# 14_Clocks.net
KiCad netlist of a schematic drawn in Altium Designer
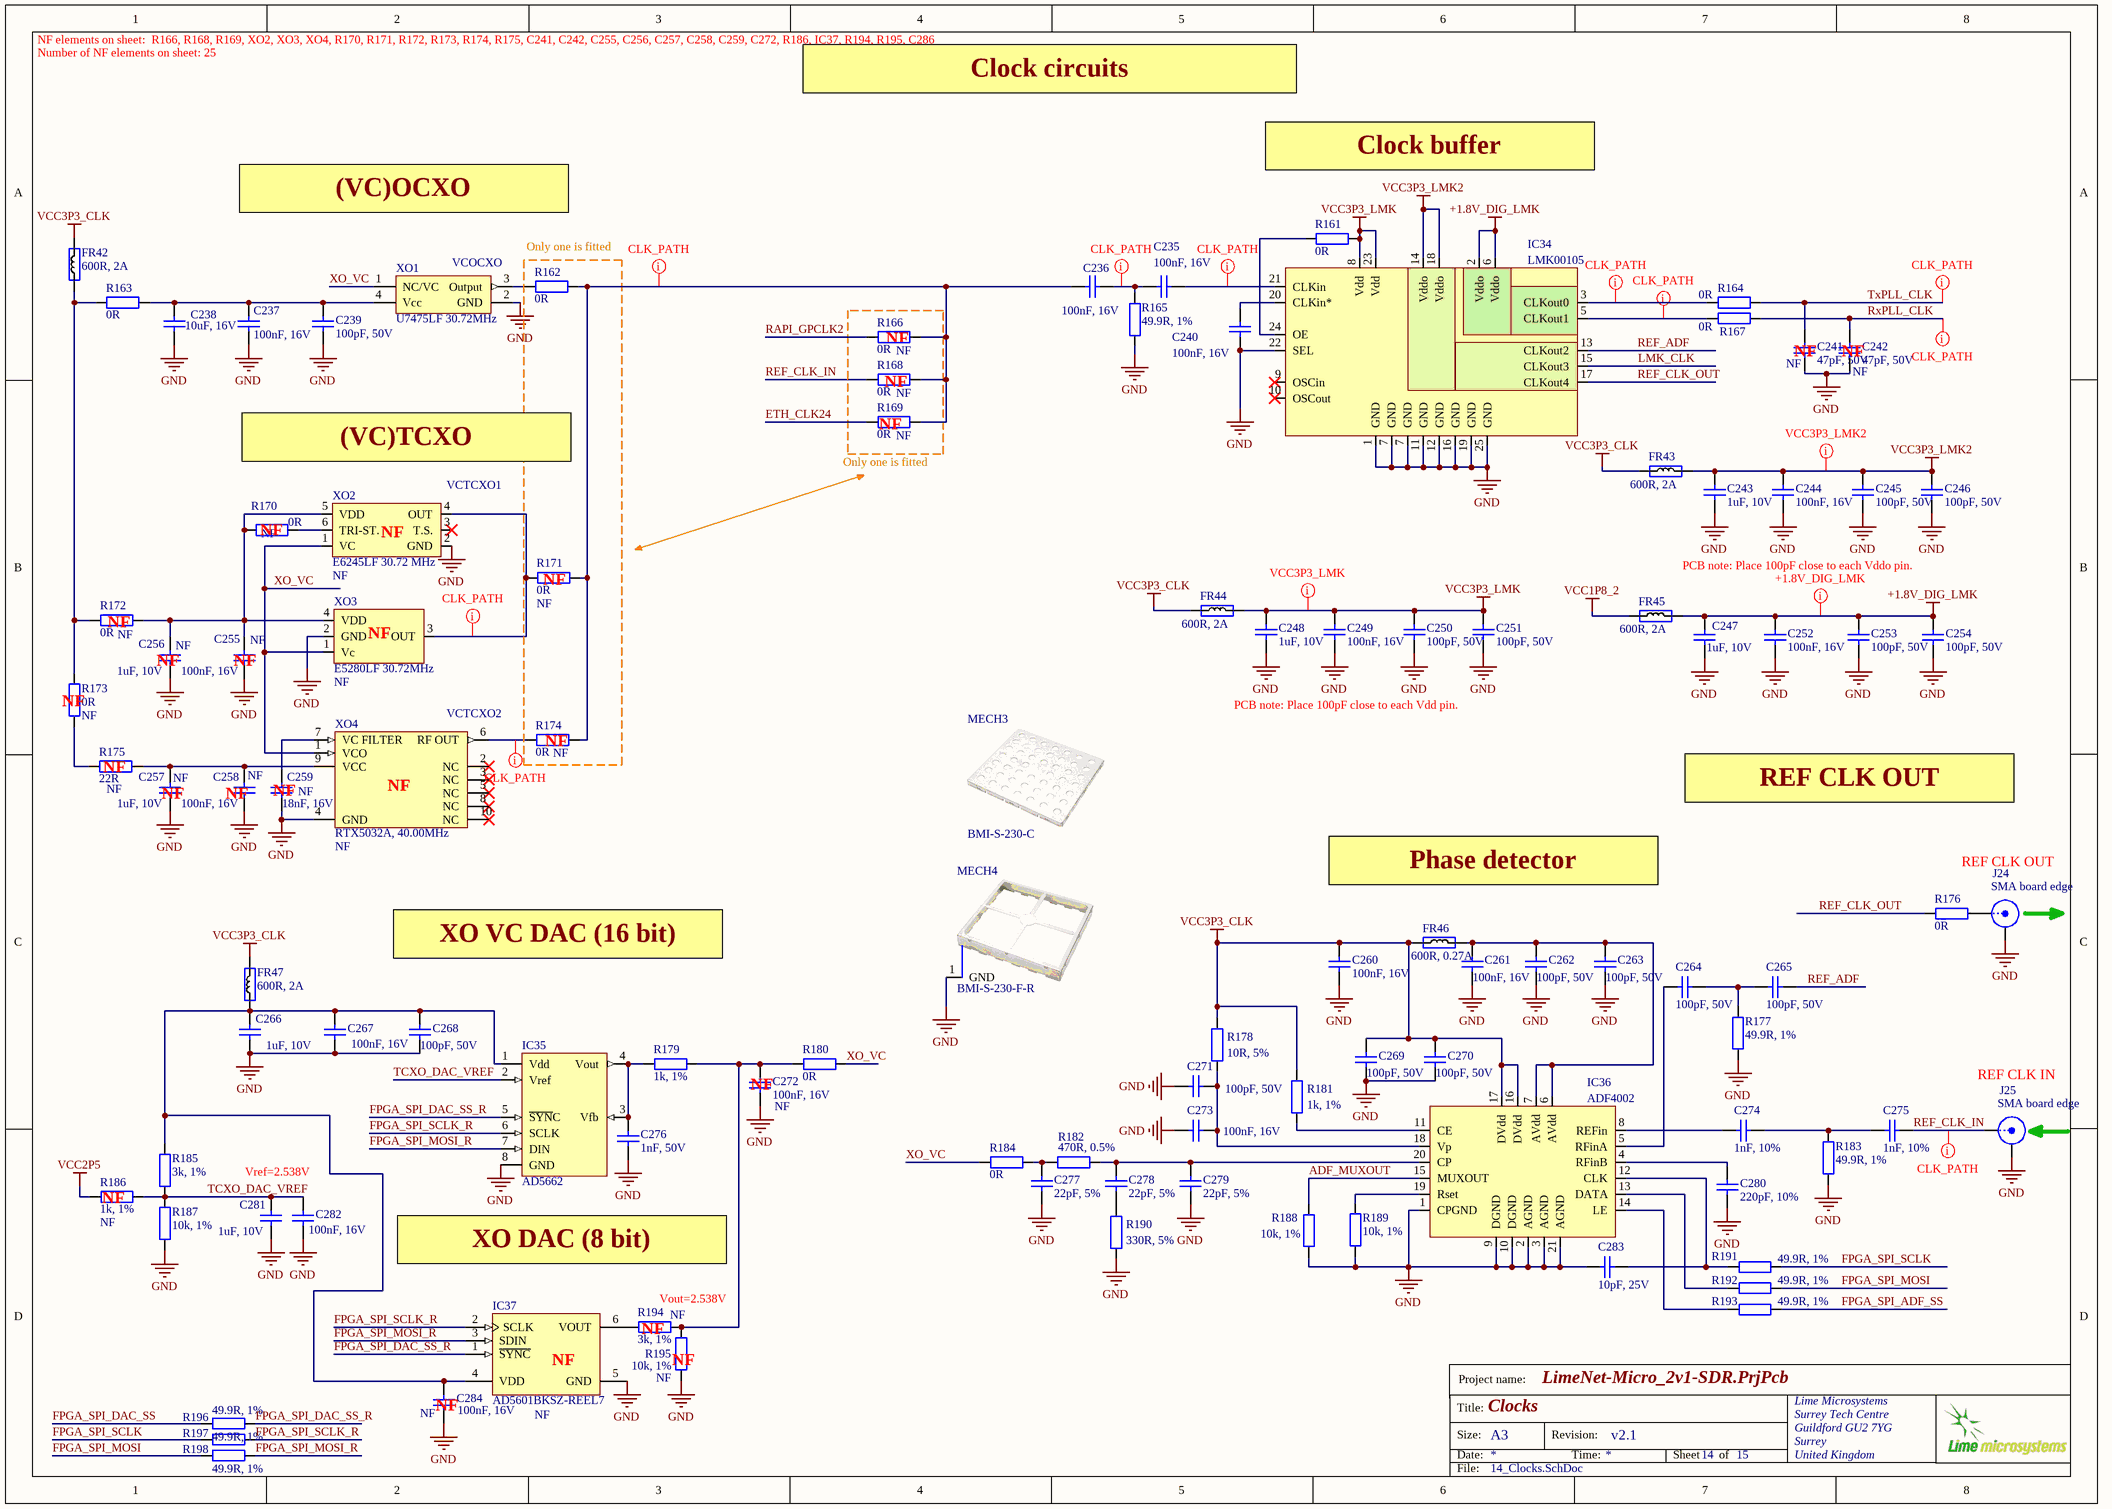
[diagram p0: 14_Clocks.SchDoc]

(export (version "E")
  (design (tool "Eeschema 10.0.6"))
  (components
    (comp (ref "C235")
      (value "100nF, 16V")
      (footprint "CAP0402")
      (fields
        (field (name "MANUFACTURER") "Murata Electronics")
        (field (name "TOLERANCE") "10 %")
        (field (name "MANUFACTURER PART NUMBER") "GRM155R71C104KA88D")
      )
      (libsource (lib "LimeMicroAltiumLib_schLib") (part "Cap_0402"))
    )
    (comp (ref "C236")
      (value "100nF, 16V")
      (footprint "CAP0402")
      (fields
        (field (name "MANUFACTURER") "Murata Electronics")
        (field (name "TOLERANCE") "10 %")
        (field (name "MANUFACTURER PART NUMBER") "GRM155R71C104KA88D")
      )
      (libsource (lib "LimeMicroAltiumLib_schLib") (part "Cap_0402"))
    )
    (comp (ref "C237")
      (value "100nF, 16V")
      (footprint "CAP0402")
      (fields
        (field (name "MANUFACTURER") "Murata Electronics")
        (field (name "TOLERANCE") "10 %")
        (field (name "MANUFACTURER PART NUMBER") "GRM155R71C104KA88D")
      )
      (libsource (lib "LimeMicroAltiumLib_schLib") (part "Cap_0402"))
    )
    (comp (ref "C238")
      (value "10uF, 16V")
      (footprint "CAP0603")
      (fields (field (name "MANUFACTURER") "Yageo") (field (name "TOLERANCE") "±20%"))
      (libsource (lib "LimeMicroAltiumLib_schLib") (part "Cap_0603"))
    )
    (comp (ref "C239")
      (value "100pF, 50V")
      (footprint "CAP0402")
      (fields (field (name "TOLERANCE") "±5%") (field (name "MANUFACTURER") "Yageo"))
      (libsource (lib "LimeMicroAltiumLib_schLib") (part "Cap_0402"))
    )
    (comp (ref "C240")
      (value "100nF, 16V")
      (footprint "CAP0402")
      (fields
        (field (name "MANUFACTURER") "Murata Electronics")
        (field (name "TOLERANCE") "10 %")
        (field (name "MANUFACTURER PART NUMBER") "GRM155R71C104KA88D")
      )
      (libsource (lib "LimeMicroAltiumLib_schLib") (part "Cap_0402"))
    )
    (comp (ref "C241")
      (value "47pF, 50V")
      (footprint "CAP0402")
      (fields
        (field (name "TOLERANCE") "±1%")
        (field (name "MANUFACTURER") "TDK Corporation")
        (field (name "ASSEMBLY INFO") "NF")
      )
      (libsource (lib "LimeMicroAltiumLib_schLib") (part "Cap_0402"))
    )
    (comp (ref "C242")
      (value "47pF, 50V")
      (footprint "CAP0402")
      (fields
        (field (name "TOLERANCE") "±1%")
        (field (name "MANUFACTURER") "TDK Corporation")
        (field (name "ASSEMBLY INFO") "NF")
      )
      (libsource (lib "LimeMicroAltiumLib_schLib") (part "Cap_0402"))
    )
    (comp (ref "C243")
      (value "1uF, 10V")
      (footprint "CAP0402")
      (description "CAP CER 1UF 10V X5R 0402")
      (fields (field (name "MANUFACTURER") "Yageo") (field (name "TOLERANCE") "±20%"))
      (libsource (lib "LimeMicroAltiumLib_schLib") (part "Cap_0402"))
    )
    (comp (ref "C244")
      (value "100nF, 16V")
      (footprint "CAP0402")
      (fields
        (field (name "MANUFACTURER") "Murata Electronics")
        (field (name "TOLERANCE") "10 %")
        (field (name "MANUFACTURER PART NUMBER") "GRM155R71C104KA88D")
      )
      (libsource (lib "LimeMicroAltiumLib_schLib") (part "Cap_0402"))
    )
    (comp (ref "C245")
      (value "100pF, 50V")
      (footprint "CAP0402")
      (fields (field (name "MANUFACTURER") "Yageo") (field (name "TOLERANCE") "±5%"))
      (libsource (lib "LimeMicroAltiumLib_schLib") (part "Cap_0402"))
    )
    (comp (ref "C246")
      (value "100pF, 50V")
      (footprint "CAP0402")
      (fields (field (name "MANUFACTURER") "Yageo") (field (name "TOLERANCE") "±5%"))
      (libsource (lib "LimeMicroAltiumLib_schLib") (part "Cap_0402"))
    )
    (comp (ref "C247")
      (value "1uF, 10V")
      (footprint "CAP0402")
      (description "CAP CER 1UF 10V X5R 0402")
      (fields (field (name "MANUFACTURER") "Yageo") (field (name "TOLERANCE") "±20%"))
      (libsource (lib "LimeMicroAltiumLib_schLib") (part "Cap_0402"))
    )
    (comp (ref "C248")
      (value "1uF, 10V")
      (footprint "CAP0402")
      (description "CAP CER 1UF 10V X5R 0402")
      (fields (field (name "MANUFACTURER") "Yageo") (field (name "TOLERANCE") "±20%"))
      (libsource (lib "LimeMicroAltiumLib_schLib") (part "Cap_0402"))
    )
    (comp (ref "C249")
      (value "100nF, 16V")
      (footprint "CAP0402")
      (fields
        (field (name "MANUFACTURER") "Murata Electronics")
        (field (name "TOLERANCE") "10 %")
        (field (name "MANUFACTURER PART NUMBER") "GRM155R71C104KA88D")
      )
      (libsource (lib "LimeMicroAltiumLib_schLib") (part "Cap_0402"))
    )
    (comp (ref "C250")
      (value "100pF, 50V")
      (footprint "CAP0402")
      (fields (field (name "MANUFACTURER") "Yageo") (field (name "TOLERANCE") "±5%"))
      (libsource (lib "LimeMicroAltiumLib_schLib") (part "Cap_0402"))
    )
    (comp (ref "C251")
      (value "100pF, 50V")
      (footprint "CAP0402")
      (fields (field (name "MANUFACTURER") "Yageo") (field (name "TOLERANCE") "±5%"))
      (libsource (lib "LimeMicroAltiumLib_schLib") (part "Cap_0402"))
    )
    (comp (ref "C252")
      (value "100nF, 16V")
      (footprint "CAP0402")
      (fields
        (field (name "MANUFACTURER") "Murata Electronics")
        (field (name "TOLERANCE") "10 %")
        (field (name "MANUFACTURER PART NUMBER") "GRM155R71C104KA88D")
      )
      (libsource (lib "LimeMicroAltiumLib_schLib") (part "Cap_0402"))
    )
    (comp (ref "C253")
      (value "100pF, 50V")
      (footprint "CAP0402")
      (fields (field (name "MANUFACTURER") "Yageo") (field (name "TOLERANCE") "±5%"))
      (libsource (lib "LimeMicroAltiumLib_schLib") (part "Cap_0402"))
    )
    (comp (ref "C254")
      (value "100pF, 50V")
      (footprint "CAP0402")
      (fields (field (name "MANUFACTURER") "Yageo") (field (name "TOLERANCE") "±5%"))
      (libsource (lib "LimeMicroAltiumLib_schLib") (part "Cap_0402"))
    )
    (comp (ref "C255")
      (value "100nF, 16V")
      (footprint "CAP0402")
      (fields
        (field (name "ASSEMBLY INFO") "NF")
        (field (name "MANUFACTURER") "Murata Electronics")
        (field (name "TOLERANCE") "10 %")
        (field (name "MANUFACTURER PART NUMBER") "GRM155R71C104KA88D")
      )
      (libsource (lib "LimeMicroAltiumLib_schLib") (part "Cap_0402"))
    )
    (comp (ref "C256")
      (value "1uF, 10V")
      (footprint "CAP0402")
      (description "CAP CER 1UF 10V X5R 0402")
      (fields
        (field (name "ASSEMBLY INFO") "NF")
        (field (name "MANUFACTURER") "Yageo")
        (field (name "TOLERANCE") "±20%")
      )
      (libsource (lib "LimeMicroAltiumLib_schLib") (part "Cap_0402"))
    )
    (comp (ref "C257")
      (value "1uF, 10V")
      (footprint "CAP0402")
      (description "CAP CER 1UF 10V X5R 0402")
      (fields
        (field (name "ASSEMBLY INFO") "NF")
        (field (name "MANUFACTURER") "Yageo")
        (field (name "TOLERANCE") "±20%")
      )
      (libsource (lib "LimeMicroAltiumLib_schLib") (part "Cap_0402"))
    )
    (comp (ref "C258")
      (value "100nF, 16V")
      (footprint "CAP0402")
      (fields
        (field (name "ASSEMBLY INFO") "NF")
        (field (name "MANUFACTURER") "Murata Electronics")
        (field (name "TOLERANCE") "10 %")
        (field (name "MANUFACTURER PART NUMBER") "GRM155R71C104KA88D")
      )
      (libsource (lib "LimeMicroAltiumLib_schLib") (part "Cap_0402"))
    )
    (comp (ref "C259")
      (value "18nF, 16V")
      (footprint "CAP0402")
      (fields
        (field (name "ASSEMBLY INFO") "NF")
        (field (name "MANUFACTURER") "Yageo")
        (field (name "TOLERANCE") "±10%")
      )
      (libsource (lib "LimeMicroAltiumLib_schLib") (part "Cap_0402"))
    )
    (comp (ref "C260")
      (value "100nF, 16V")
      (footprint "CAP0402")
      (fields
        (field (name "MANUFACTURER") "Murata Electronics")
        (field (name "TOLERANCE") "10 %")
        (field (name "MANUFACTURER PART NUMBER") "GRM155R71C104KA88D")
      )
      (libsource (lib "LimeMicroAltiumLib_schLib") (part "Cap_0402"))
    )
    (comp (ref "C261")
      (value "100nF, 16V")
      (footprint "CAP0402")
      (fields
        (field (name "MANUFACTURER") "Murata Electronics")
        (field (name "TOLERANCE") "10 %")
        (field (name "MANUFACTURER PART NUMBER") "GRM155R71C104KA88D")
      )
      (libsource (lib "LimeMicroAltiumLib_schLib") (part "Cap_0402"))
    )
    (comp (ref "C262")
      (value "100pF, 50V")
      (footprint "CAP0402")
      (fields (field (name "MANUFACTURER") "Yageo") (field (name "TOLERANCE") "±5%"))
      (libsource (lib "LimeMicroAltiumLib_schLib") (part "Cap_0402"))
    )
    (comp (ref "C263")
      (value "100pF, 50V")
      (footprint "CAP0402")
      (fields (field (name "MANUFACTURER") "Yageo") (field (name "TOLERANCE") "±5%"))
      (libsource (lib "LimeMicroAltiumLib_schLib") (part "Cap_0402"))
    )
    (comp (ref "C264")
      (value "100pF, 50V")
      (footprint "CAP0402")
      (fields (field (name "MANUFACTURER") "Yageo") (field (name "TOLERANCE") "±5%"))
      (libsource (lib "LimeMicroAltiumLib_schLib") (part "Cap_0402"))
    )
    (comp (ref "C265")
      (value "100pF, 50V")
      (footprint "CAP0402")
      (fields (field (name "MANUFACTURER") "Yageo") (field (name "TOLERANCE") "±5%"))
      (libsource (lib "LimeMicroAltiumLib_schLib") (part "Cap_0402"))
    )
    (comp (ref "C266")
      (value "1uF, 10V")
      (footprint "CAP0402")
      (description "CAP CER 1UF 10V X5R 0402")
      (fields (field (name "MANUFACTURER") "Yageo") (field (name "TOLERANCE") "±20%"))
      (libsource (lib "LimeMicroAltiumLib_schLib") (part "Cap_0402"))
    )
    (comp (ref "C267")
      (value "100nF, 16V")
      (footprint "CAP0402")
      (fields
        (field (name "TOLERANCE") "10 %")
        (field (name "MANUFACTURER") "Murata Electronics")
        (field (name "MANUFACTURER PART NUMBER") "GRM155R71C104KA88D")
      )
      (libsource (lib "LimeFPGAboard_schLib") (part "Cap_0603"))
    )
    (comp (ref "C268")
      (value "100pF, 50V")
      (footprint "CAP0402")
      (fields (field (name "MANUFACTURER") "Yageo") (field (name "TOLERANCE") "±5%"))
      (libsource (lib "LimeMicroAltiumLib_schLib") (part "Cap_0402"))
    )
    (comp (ref "C269")
      (value "100pF, 50V")
      (footprint "CAP0402")
      (fields (field (name "MANUFACTURER") "Yageo") (field (name "TOLERANCE") "±5%"))
      (libsource (lib "LimeMicroAltiumLib_schLib") (part "Cap_0402"))
    )
    (comp (ref "C270")
      (value "100pF, 50V")
      (footprint "CAP0402")
      (fields (field (name "MANUFACTURER") "Yageo") (field (name "TOLERANCE") "±5%"))
      (libsource (lib "LimeMicroAltiumLib_schLib") (part "Cap_0402"))
    )
    (comp (ref "C271")
      (value "100pF, 50V")
      (footprint "CAP0402")
      (fields (field (name "MANUFACTURER") "Yageo") (field (name "TOLERANCE") "±5%"))
      (libsource (lib "LimeMicroAltiumLib_schLib") (part "Cap_0402"))
    )
    (comp (ref "C272")
      (value "100nF, 16V")
      (footprint "CAP0402")
      (fields
        (field (name "ASSEMBLY INFO") "NF")
        (field (name "MANUFACTURER") "Murata Electronics")
        (field (name "TOLERANCE") "10 %")
        (field (name "MANUFACTURER PART NUMBER") "GRM155R71C104KA88D")
      )
      (libsource (lib "LimeMicroAltiumLib_schLib") (part "Cap_0402"))
    )
    (comp (ref "C273")
      (value "100nF, 16V")
      (footprint "CAP0402")
      (fields
        (field (name "MANUFACTURER") "Murata Electronics")
        (field (name "TOLERANCE") "10 %")
        (field (name "MANUFACTURER PART NUMBER") "GRM155R71C104KA88D")
      )
      (libsource (lib "LimeMicroAltiumLib_schLib") (part "Cap_0402"))
    )
    (comp (ref "C274")
      (value "1nF, 10%")
      (footprint "CAP0402")
      (fields (field (name "TOLERANCE") "10 %") (field (name "MANUFACTURER") "Murata Electronics"))
      (libsource (lib "LimeMicroAltiumLib_schLib") (part "Cap_0402"))
    )
    (comp (ref "C275")
      (value "1nF, 10%")
      (footprint "CAP0402")
      (fields (field (name "TOLERANCE") "10 %") (field (name "MANUFACTURER") "Murata Electronics"))
      (libsource (lib "LimeMicroAltiumLib_schLib") (part "Cap_0402"))
    )
    (comp (ref "C276")
      (value "1nF, 50V")
      (footprint "CAP0402")
      (fields
        (field (name "TOLERANCE") "±10%")
        (field (name "MANUFACTURER") "Murata Electronics North America")
      )
      (libsource (lib "LimeMicroAltiumLib_schLib") (part "Cap_0402"))
    )
    (comp (ref "C277")
      (value "22pF, 5%")
      (footprint "CAP0402")
      (fields (field (name "TOLERANCE") "±5%") (field (name "MANUFACTURER") "Yageo"))
      (libsource (lib "LimeMicroAltiumLib_schLib") (part "Cap_0402"))
    )
    (comp (ref "C278")
      (value "22pF, 5%")
      (footprint "CAP0402")
      (fields (field (name "TOLERANCE") "±5%") (field (name "MANUFACTURER") "Yageo"))
      (libsource (lib "LimeMicroAltiumLib_schLib") (part "Cap_0402"))
    )
    (comp (ref "C279")
      (value "22pF, 5%")
      (footprint "CAP0402")
      (fields (field (name "TOLERANCE") "±5%") (field (name "MANUFACTURER") "Yageo"))
      (libsource (lib "LimeMicroAltiumLib_schLib") (part "Cap_0402"))
    )
    (comp (ref "C280")
      (value "220pF, 10%")
      (footprint "CAP0402")
      (fields (field (name "MANUFACTURER") "Yageo") (field (name "TOLERANCE") "±10%"))
      (libsource (lib "LimeMicroAltiumLib_schLib") (part "Cap_0402"))
    )
    (comp (ref "C281")
      (value "1uF, 10V")
      (footprint "CAP0402")
      (description "CAP CER 1UF 10V X5R 0402")
      (fields (field (name "MANUFACTURER") "Yageo") (field (name "TOLERANCE") "±20%"))
      (libsource (lib "LimeMicroAltiumLib_schLib") (part "Cap_0402"))
    )
    (comp (ref "C282")
      (value "100nF, 16V")
      (footprint "CAP0402")
      (fields
        (field (name "TOLERANCE") "10 %")
        (field (name "MANUFACTURER") "Murata Electronics")
        (field (name "MANUFACTURER PART NUMBER") "GRM155R71C104KA88D")
      )
      (libsource (lib "LimeFPGAboard_schLib") (part "Cap_0603"))
    )
    (comp (ref "C283")
      (value "10pF, 25V")
      (footprint "CAP0402")
      (fields (field (name "MANUFACTURER") "AVX"))
      (libsource (lib "LimeMicroAltiumLib_schLib") (part "Cap_0402"))
    )
    (comp (ref "C284")
      (value "100nF, 16V")
      (footprint "CAP0402")
      (fields
        (field (name "TOLERANCE") "10 %")
        (field (name "MANUFACTURER") "Murata Electronics")
        (field (name "MANUFACTURER PART NUMBER") "GRM155R71C104KA88D")
        (field (name "ASSEMBLY INFO") "NF")
      )
      (libsource (lib "LimeFPGAboard_schLib") (part "Cap_0603"))
    )
    (comp (ref "FR42")
      (value "600R, 2A")
      (footprint "RES0805")
      (fields (field (name "MANUFACTURER") "TDK Corporation"))
      (libsource (lib "LimeFPGAboard_schLib") (part "Ferrite"))
    )
    (comp (ref "FR43")
      (value "600R, 2A")
      (footprint "RES0805")
      (fields (field (name "MANUFACTURER") "TDK Corporation"))
      (libsource (lib "LimeMicroAltiumLib_schLib") (part "Ferrite"))
    )
    (comp (ref "FR44")
      (value "600R, 2A")
      (footprint "RES0805")
      (fields (field (name "MANUFACTURER") "TDK Corporation"))
      (libsource (lib "LimeMicroAltiumLib_schLib") (part "Ferrite"))
    )
    (comp (ref "FR45")
      (value "600R, 2A")
      (footprint "RES0805")
      (fields (field (name "MANUFACTURER") "TDK Corporation"))
      (libsource (lib "LimeMicroAltiumLib_schLib") (part "Ferrite"))
    )
    (comp (ref "FR46")
      (value "600R, 0.27A")
      (footprint "RES0201")
      (fields (field (name "MANUFACTURER") "Taiyo Yuden"))
      (libsource (lib "LimeMicroAltiumLib_schLib") (part "Ferrite"))
    )
    (comp (ref "FR47")
      (value "600R, 2A")
      (footprint "RES0805")
      (fields (field (name "MANUFACTURER") "TDK Corporation"))
      (libsource (lib "LimeMicroAltiumLib_schLib") (part "Ferrite"))
    )
    (comp (ref "IC34")
      (value "LMK00105")
      (footprint "LMK00105SQ")
      (fields (field (name "MANUFACTURER") "Texas Instruments"))
      (libsource (lib "LimeMicroAltiumLib_schLib") (part "LMK00105"))
    )
    (comp (ref "IC35")
      (value "AD5662")
      (footprint "AD5662_SOT23-8")
      (fields (field (name "MANUFACTURER") "Analog Devices Inc."))
      (libsource (lib "LimeMicroAltiumLib_schLib") (part "AD5662"))
    )
    (comp (ref "IC36")
      (value "ADF4002")
      (footprint "ADF4002")
      (fields (field (name "MANUFACTURER") "Analog Devices Inc"))
      (libsource (lib "LimeMicroAltiumLib_schLib") (part "ADF4002"))
    )
    (comp (ref "IC37")
      (value "AD5601BKSZ-REEL7")
      (footprint "AD5601_SOT23-6")
      (fields
        (field (name "GENERIC PART NUMBER") "AD5601")
        (field (name "MANUFACTURER") "Analog Devices")
        (field (name "ASSEMBLY INFO") "NF")
      )
      (libsource (lib "LimeMicroAltiumLib_schLib") (part "AD5601BKSZ-REEL7"))
    )
    (comp (ref "J24")
      (value "SMA board edge")
      (footprint "SMA_connector_board_edge_SM")
      (description "CONN SMA JACK STR 50OHM EDGE MNT")
      (fields (field (name "MANUFACTURER") "RF Solutions"))
      (libsource (lib "LimeMicroAltiumLib_schLib") (part "RF_IF_connector"))
    )
    (comp (ref "J25")
      (value "SMA board edge")
      (footprint "SMA_connector_board_edge_SM")
      (description "CONN SMA JACK STR 50OHM EDGE MNT")
      (fields (field (name "MANUFACTURER") "RF Solutions"))
      (libsource (lib "LimeMicroAltiumLib_schLib") (part "RF_IF_connector"))
    )
    (comp (ref "MECH3")
      (value "BMI-S-230-C")
      (fields (field (name "MANUFACTURER") "Laird Technologies EMI"))
      (libsource (lib "LimeMicroAltiumLib_schLib_r01") (part "RFI_SHIELD_2_cover"))
    )
    (comp (ref "MECH4")
      (value "BMI-S-230-F-R")
      (footprint "RFI_SHIELD_BMI-S-230-F-R")
      (fields (field (name "MANUFACTURER") "Laird Technologies EMI"))
      (libsource (lib "LimeMicroAltiumLib_schLib_r01") (part "RFI_SHIELD_2_frame"))
    )
    (comp (ref "R161")
      (value "0R")
      (footprint "RES0402")
      (fields (field (name "MANUFACTURER") "Yageo") (field (name "TOLERANCE") "Jumper"))
      (libsource (lib "LimeMicroAltiumLib_schLib") (part "Res_0402"))
    )
    (comp (ref "R162")
      (value "0R")
      (footprint "RES0402_v2")
      (fields (field (name "MANUFACTURER") "Yageo") (field (name "TOLERANCE") "Jumper"))
      (libsource (lib "LimeMicroAltiumLib_schLib") (part "Res_0402"))
    )
    (comp (ref "R163")
      (value "0R")
      (footprint "RES0402")
      (fields (field (name "MANUFACTURER") "Yageo") (field (name "TOLERANCE") "Jumper"))
      (libsource (lib "LimeMicroAltiumLib_schLib") (part "Res_0402"))
    )
    (comp (ref "R164")
      (value "0R")
      (footprint "RES0402")
      (fields (field (name "MANUFACTURER") "Yageo") (field (name "TOLERANCE") "Jumper"))
      (libsource (lib "LimeMicroAltiumLib_schLib") (part "Res_0402"))
    )
    (comp (ref "R165")
      (value "49.9R, 1%")
      (footprint "RES0402")
      (fields
        (field (name "TOLERANCE") "±1%")
        (field (name "MANUFACTURER") "Samsung Electro-Mechanics America, Inc.")
      )
      (libsource (lib "LimeMicroAltiumLib_schLib") (part "Res_0402"))
    )
    (comp (ref "R166")
      (value "0R")
      (footprint "RES0402_v2")
      (fields
        (field (name "ASSEMBLY INFO") "NF")
        (field (name "MANUFACTURER") "Yageo")
        (field (name "TOLERANCE") "Jumper")
      )
      (libsource (lib "LimeMicroAltiumLib_schLib") (part "Res_0402"))
    )
    (comp (ref "R167")
      (value "0R")
      (footprint "RES0402")
      (fields (field (name "MANUFACTURER") "Yageo") (field (name "TOLERANCE") "Jumper"))
      (libsource (lib "LimeMicroAltiumLib_schLib") (part "Res_0402"))
    )
    (comp (ref "R168")
      (value "0R")
      (footprint "RES0402_v2")
      (fields
        (field (name "ASSEMBLY INFO") "NF")
        (field (name "MANUFACTURER") "Yageo")
        (field (name "TOLERANCE") "Jumper")
      )
      (libsource (lib "LimeMicroAltiumLib_schLib") (part "Res_0402"))
    )
    (comp (ref "R169")
      (value "0R")
      (footprint "RES0402_v2")
      (fields
        (field (name "ASSEMBLY INFO") "NF")
        (field (name "MANUFACTURER") "Yageo")
        (field (name "TOLERANCE") "Jumper")
      )
      (libsource (lib "LimeMicroAltiumLib_schLib") (part "Res_0402"))
    )
    (comp (ref "R170")
      (value "0R")
      (footprint "RES0402")
      (fields
        (field (name "ASSEMBLY INFO") "NF")
        (field (name "MANUFACTURER") "Yageo")
        (field (name "TOLERANCE") "Jumper")
      )
      (libsource (lib "LimeMicroAltiumLib_schLib") (part "Res_0402"))
    )
    (comp (ref "R171")
      (value "0R")
      (footprint "RES0402_v2")
      (fields
        (field (name "ASSEMBLY INFO") "NF")
        (field (name "MANUFACTURER") "Yageo")
        (field (name "TOLERANCE") "Jumper")
      )
      (libsource (lib "LimeMicroAltiumLib_schLib") (part "Res_0402"))
    )
    (comp (ref "R172")
      (value "0R")
      (footprint "RES0402")
      (fields
        (field (name "MANUFACTURER") "Yageo")
        (field (name "TOLERANCE") "Jumper")
        (field (name "ASSEMBLY INFO") "NF")
      )
      (libsource (lib "") (part "Res_0402_1"))
    )
    (comp (ref "R173")
      (value "0R")
      (footprint "RES0402")
      (fields
        (field (name "ASSEMBLY INFO") "NF")
        (field (name "MANUFACTURER") "Yageo")
        (field (name "TOLERANCE") "Jumper")
      )
      (libsource (lib "LimeMicroAltiumLib_schLib") (part "Res_0402"))
    )
    (comp (ref "R174")
      (value "0R")
      (footprint "RES0402_v2")
      (fields
        (field (name "ASSEMBLY INFO") "NF")
        (field (name "MANUFACTURER") "Yageo")
        (field (name "TOLERANCE") "Jumper")
      )
      (libsource (lib "LimeMicroAltiumLib_schLib") (part "Res_0402"))
    )
    (comp (ref "R175")
      (value "22R")
      (footprint "RES0402")
      (fields
        (field (name "TOLERANCE") "±1%")
        (field (name "MANUFACTURER") "Yageo")
        (field (name "ASSEMBLY INFO") "NF")
      )
      (libsource (lib "LimeFPGAboard_schLib") (part "Res_0402"))
    )
    (comp (ref "R176")
      (value "0R")
      (footprint "RES0402")
      (fields (field (name "MANUFACTURER") "Yageo") (field (name "TOLERANCE") "Jumper"))
      (libsource (lib "LimeMicroAltiumLib_schLib") (part "Res_0402"))
    )
    (comp (ref "R177")
      (value "49.9R, 1%")
      (footprint "RES0402")
      (fields
        (field (name "TOLERANCE") "±1%")
        (field (name "MANUFACTURER") "Samsung Electro-Mechanics America, Inc.")
      )
      (libsource (lib "LimeMicroAltiumLib_schLib") (part "Res_0402"))
    )
    (comp (ref "R178")
      (value "10R, 5%")
      (footprint "RES0402")
      (fields (field (name "TOLERANCE") "±5%") (field (name "MANUFACTURER") "Yageo"))
      (libsource (lib "LimeMicroAltiumLib_schLib") (part "Res_0402"))
    )
    (comp (ref "R179")
      (value "1k, 1%")
      (footprint "RES0402")
      (fields (field (name "MANUFACTURER") "Stackpole Electronics Inc") (field (name "TOLERANCE") "±1%"))
      (libsource (lib "LimeMicroAltiumLib_schLib") (part "Res_0402"))
    )
    (comp (ref "R180")
      (value "0R")
      (footprint "RES0402")
      (fields (field (name "MANUFACTURER") "Yageo") (field (name "TOLERANCE") "Jumper"))
      (libsource (lib "LimeMicroAltiumLib_schLib") (part "Res_0402"))
    )
    (comp (ref "R181")
      (value "1k, 1%")
      (footprint "RES0402")
      (fields (field (name "MANUFACTURER") "Stackpole Electronics Inc") (field (name "TOLERANCE") "±1%"))
      (libsource (lib "LimeMicroAltiumLib_schLib") (part "Res_0402"))
    )
    (comp (ref "R182")
      (value "470R, 0.5%")
      (footprint "RES0402")
      (fields
        (field (name "TOLERANCE") "±0.5%")
        (field (name "MANUFACTURER") "Panasonic Electronic Components")
      )
      (libsource (lib "LimeMicroAltiumLib_schLib") (part "Res_0402"))
    )
    (comp (ref "R183")
      (value "49.9R, 1%")
      (footprint "RES0402")
      (fields
        (field (name "TOLERANCE") "±1%")
        (field (name "MANUFACTURER") "Samsung Electro-Mechanics America, Inc.")
      )
      (libsource (lib "LimeMicroAltiumLib_schLib") (part "Res_0402"))
    )
    (comp (ref "R184")
      (value "0R")
      (footprint "RES0402")
      (fields (field (name "MANUFACTURER") "Yageo") (field (name "TOLERANCE") "Jumper"))
      (libsource (lib "LimeMicroAltiumLib_schLib") (part "Res_0402"))
    )
    (comp (ref "R185")
      (value "3k, 1%")
      (footprint "RES0402")
      (fields (field (name "TOLERANCE") "±1%") (field (name "MANUFACTURER") "Vishay Dale"))
      (libsource (lib "LimeMicroAltiumLib_schLib") (part "Res_0402"))
    )
    (comp (ref "R186")
      (value "1k, 1%")
      (footprint "RES0402")
      (fields
        (field (name "ASSEMBLY INFO") "NF")
        (field (name "MANUFACTURER") "Stackpole Electronics Inc")
        (field (name "TOLERANCE") "±1%")
      )
      (libsource (lib "LimeMicroAltiumLib_schLib") (part "Res_0402"))
    )
    (comp (ref "R187")
      (value "10k, 1%")
      (footprint "RES0402")
      (fields (field (name "MANUFACTURER") "Yageo") (field (name "TOLERANCE") "±1%"))
      (libsource (lib "LimeMicroAltiumLib_schLib") (part "Res_0402"))
    )
    (comp (ref "R188")
      (value "10k, 1%")
      (footprint "RES0402")
      (fields (field (name "MANUFACTURER") "Yageo") (field (name "TOLERANCE") "±1%"))
      (libsource (lib "LimeMicroAltiumLib_schLib") (part "Res_0402"))
    )
    (comp (ref "R189")
      (value "10k, 1%")
      (footprint "RES0402")
      (fields (field (name "MANUFACTURER") "Yageo") (field (name "TOLERANCE") "±1%"))
      (libsource (lib "LimeMicroAltiumLib_schLib") (part "Res_0402"))
    )
    (comp (ref "R190")
      (value "330R, 5%")
      (footprint "RES0402")
      (fields (field (name "MANUFACTURER") "Yageo") (field (name "TOLERANCE") "±5%"))
      (libsource (lib "LimeMicroAltiumLib_schLib") (part "Res_0402"))
    )
    (comp (ref "R191")
      (value "49.9R, 1%")
      (footprint "RES0402")
      (fields
        (field (name "TOLERANCE") "±1%")
        (field (name "MANUFACTURER") "Samsung Electro-Mechanics America, Inc.")
      )
      (libsource (lib "LimeMicroAltiumLib_schLib") (part "Res_0402"))
    )
    (comp (ref "R192")
      (value "49.9R, 1%")
      (footprint "RES0402")
      (fields
        (field (name "TOLERANCE") "±1%")
        (field (name "MANUFACTURER") "Samsung Electro-Mechanics America, Inc.")
      )
      (libsource (lib "LimeMicroAltiumLib_schLib") (part "Res_0402"))
    )
    (comp (ref "R193")
      (value "49.9R, 1%")
      (footprint "RES0402")
      (fields
        (field (name "TOLERANCE") "±1%")
        (field (name "MANUFACTURER") "Samsung Electro-Mechanics America, Inc.")
      )
      (libsource (lib "LimeMicroAltiumLib_schLib") (part "Res_0402"))
    )
    (comp (ref "R194")
      (value "3k, 1%")
      (footprint "RES0402")
      (fields
        (field (name "ASSEMBLY INFO") "NF")
        (field (name "TOLERANCE") "±1%")
        (field (name "MANUFACTURER") "Vishay Dale")
      )
      (libsource (lib "LimeMicroAltiumLib_schLib") (part "Res_0402"))
    )
    (comp (ref "R195")
      (value "10k, 1%")
      (footprint "RES0402")
      (fields
        (field (name "ASSEMBLY INFO") "NF")
        (field (name "MANUFACTURER") "Yageo")
        (field (name "TOLERANCE") "±1%")
      )
      (libsource (lib "LimeMicroAltiumLib_schLib") (part "Res_0402"))
    )
    (comp (ref "R196")
      (value "49.9R, 1%")
      (footprint "RES0402")
      (fields
        (field (name "TOLERANCE") "±1%")
        (field (name "MANUFACTURER") "Samsung Electro-Mechanics America, Inc.")
      )
      (libsource (lib "LimeMicroAltiumLib_schLib") (part "Res_0402"))
    )
    (comp (ref "R197")
      (value "49.9R, 1%")
      (footprint "RES0402")
      (fields
        (field (name "TOLERANCE") "±1%")
        (field (name "MANUFACTURER") "Samsung Electro-Mechanics America, Inc.")
      )
      (libsource (lib "LimeMicroAltiumLib_schLib") (part "Res_0402"))
    )
    (comp (ref "R198")
      (value "49.9R, 1%")
      (footprint "RES0402")
      (fields
        (field (name "TOLERANCE") "±1%")
        (field (name "MANUFACTURER") "Samsung Electro-Mechanics America, Inc.")
      )
      (libsource (lib "LimeMicroAltiumLib_schLib") (part "Res_0402"))
    )
    (comp (ref "XO1")
      (value "U7475LF 30.72MHz")
      (footprint "AOCJYR-10.000MHz")
      (fields (field (name "MANUFACTURER") "Rakon"))
      (libsource (lib "LimeMicroAltiumLib_schLib") (part "AOCJYR-10.000MHz"))
    )
    (comp (ref "XO2")
      (value "E6245LF 30.72 MHz")
      (footprint "RAKON_RPT7050A")
      (fields (field (name "ASSEMBLY INFO") "NF") (field (name "MANUFACTURER") "Rakon"))
      (libsource (lib "LimeMicroAltiumLib_schLib") (part "RPT7050A"))
    )
    (comp (ref "XO3")
      (value "E5280LF 30.72MHz")
      (footprint "RAKON_TXCO")
      (fields (field (name "ASSEMBLY INFO") "NF") (field (name "MANUFACTURER") "Rakon"))
      (libsource (lib "LimeMicroAltiumLib_schLib") (part "TXCO"))
    )
    (comp (ref "XO4")
      (value "RTX5032A, 40.00MHz")
      (footprint "RAKON_RTX5032A")
      (fields (field (name "ASSEMBLY INFO") "NF") (field (name "MANUFACTURER") "Rakon"))
      (libsource (lib "LimeMicroAltiumLib_schLib") (part "Rakon_RTX5032A"))
    )
  )
  (nets
    (net (code "1") (name "+1.8V_DIG_LMK") (class "Default")
      (node (ref "C247") (pin "2") (pinfunction "2_2") (pintype "passive"))
      (node (ref "C252") (pin "2") (pinfunction "2_2") (pintype "passive"))
      (node (ref "C253") (pin "2") (pinfunction "2_2") (pintype "passive"))
      (node (ref "C254") (pin "2") (pinfunction "2_2") (pintype "passive"))
      (node (ref "FR45") (pin "2") (pinfunction "2_2") (pintype "passive"))
      (node (ref "IC34") (pin "2") (pinfunction "Vddo_2") (pintype "passive"))
      (node (ref "IC34") (pin "6") (pinfunction "Vddo_6") (pintype "passive"))
    )
    (net (code "2") (name "/ADF_MUXOUT") (class "Default")
      (node (ref "IC36") (pin "15") (pinfunction "MUXOUT_15") (pintype "passive"))
      (node (ref "R188") (pin "1") (pinfunction "1_1") (pintype "passive"))
    )
    (net (code "3") (name "/ETH_CLK24") (class "Default")
      (node (ref "R169") (pin "2") (pinfunction "2_2") (pintype "passive"))
    )
    (net (code "4") (name "/FPGA_SPI_ADF_SS") (class "Default")
      (node (ref "R193") (pin "1") (pinfunction "1_1") (pintype "passive"))
    )
    (net (code "5") (name "/FPGA_SPI_DAC_SS") (class "Default")
      (node (ref "R196") (pin "2") (pinfunction "2_2") (pintype "passive"))
    )
    (net (code "6") (name "/FPGA_SPI_DAC_SS_R") (class "Default")
      (node (ref "IC35") (pin "5") (pinfunction "~{SYN}C_5") (pintype "input"))
      (node (ref "IC37") (pin "1") (pinfunction "~{SYNC}_1") (pintype "input"))
      (node (ref "R196") (pin "1") (pinfunction "1_1") (pintype "passive"))
    )
    (net (code "7") (name "/FPGA_SPI_MOSI") (class "Default")
      (node (ref "R192") (pin "1") (pinfunction "1_1") (pintype "passive"))
      (node (ref "R198") (pin "2") (pinfunction "2_2") (pintype "passive"))
    )
    (net (code "8") (name "/FPGA_SPI_MOSI_R") (class "Default")
      (node (ref "IC35") (pin "7") (pinfunction "DIN_7") (pintype "input"))
      (node (ref "IC37") (pin "3") (pinfunction "SDIN_3") (pintype "input"))
      (node (ref "R198") (pin "1") (pinfunction "1_1") (pintype "passive"))
    )
    (net (code "9") (name "/FPGA_SPI_SCLK") (class "Default")
      (node (ref "R191") (pin "1") (pinfunction "1_1") (pintype "passive"))
      (node (ref "R197") (pin "2") (pinfunction "2_2") (pintype "passive"))
    )
    (net (code "10") (name "/FPGA_SPI_SCLK_R") (class "Default")
      (node (ref "IC35") (pin "6") (pinfunction "SCLK_6") (pintype "input"))
      (node (ref "IC37") (pin "2") (pinfunction "SCLK_2") (pintype "input"))
      (node (ref "R197") (pin "1") (pinfunction "1_1") (pintype "passive"))
    )
    (net (code "11") (name "/LMK_CLK") (class "Default")
      (node (ref "IC34") (pin "15") (pinfunction "CLKout3_15") (pintype "passive"))
    )
    (net (code "12") (name "/RAPI_GPCLK2") (class "Default")
      (node (ref "R166") (pin "2") (pinfunction "2_2") (pintype "passive"))
    )
    (net (code "13") (name "/REF_ADF") (class "Default")
      (node (ref "C265") (pin "2") (pinfunction "2_2") (pintype "passive"))
      (node (ref "IC34") (pin "13") (pinfunction "CLKout2_13") (pintype "passive"))
    )
    (net (code "14") (name "/REF_CLK_IN") (class "Default")
      (node (ref "C275") (pin "1") (pinfunction "1_1") (pintype "passive"))
      (node (ref "J25") (pin "1") (pinfunction "X_1") (pintype "passive"))
      (node (ref "R168") (pin "2") (pinfunction "2_2") (pintype "passive"))
    )
    (net (code "15") (name "/REF_CLK_OUT") (class "Default")
      (node (ref "IC34") (pin "17") (pinfunction "CLKout4_17") (pintype "passive"))
      (node (ref "R176") (pin "2") (pinfunction "2_2") (pintype "passive"))
    )
    (net (code "16") (name "/RxPLL_CLK") (class "Default")
      (node (ref "C242") (pin "2") (pinfunction "2_2") (pintype "passive"))
      (node (ref "R167") (pin "1") (pinfunction "1_1") (pintype "passive"))
    )
    (net (code "17") (name "/TCXO_DAC_VREF") (class "Default")
      (node (ref "C281") (pin "2") (pinfunction "2_2") (pintype "passive"))
      (node (ref "C282") (pin "1") (pinfunction "1_1") (pintype "passive"))
      (node (ref "IC35") (pin "2") (pinfunction "Vref_2") (pintype "input"))
      (node (ref "R185") (pin "1") (pinfunction "1_1") (pintype "passive"))
      (node (ref "R186") (pin "1") (pinfunction "1_1") (pintype "passive"))
      (node (ref "R187") (pin "1") (pinfunction "1_1") (pintype "passive"))
    )
    (net (code "18") (name "/TxPLL_CLK") (class "Default")
      (node (ref "C241") (pin "2") (pinfunction "2_2") (pintype "passive"))
      (node (ref "R164") (pin "1") (pinfunction "1_1") (pintype "passive"))
    )
    (net (code "19") (name "/XO_VC") (class "Default")
      (node (ref "R180") (pin "1") (pinfunction "1_1") (pintype "passive"))
      (node (ref "R184") (pin "2") (pinfunction "2_2") (pintype "passive"))
      (node (ref "XO1") (pin "1") (pinfunction "NC/VC_1") (pintype "passive"))
      (node (ref "XO2") (pin "1") (pinfunction "VC_1") (pintype "passive"))
      (node (ref "XO3") (pin "1") (pinfunction "Vc_1") (pintype "passive"))
      (node (ref "XO4") (pin "1") (pinfunction "VCO_1") (pintype "input"))
    )
    (net (code "20") (name "GND") (class "Default")
      (node (ref "C237") (pin "1") (pinfunction "1_1") (pintype "passive"))
      (node (ref "C238") (pin "1") (pinfunction "1_1") (pintype "passive"))
      (node (ref "C239") (pin "2") (pinfunction "2_2") (pintype "passive"))
      (node (ref "C240") (pin "1") (pinfunction "1_1") (pintype "passive"))
      (node (ref "C241") (pin "1") (pinfunction "1_1") (pintype "passive"))
      (node (ref "C242") (pin "1") (pinfunction "1_1") (pintype "passive"))
      (node (ref "C243") (pin "1") (pinfunction "1_1") (pintype "passive"))
      (node (ref "C244") (pin "1") (pinfunction "1_1") (pintype "passive"))
      (node (ref "C245") (pin "1") (pinfunction "1_1") (pintype "passive"))
      (node (ref "C246") (pin "1") (pinfunction "1_1") (pintype "passive"))
      (node (ref "C247") (pin "1") (pinfunction "1_1") (pintype "passive"))
      (node (ref "C248") (pin "1") (pinfunction "1_1") (pintype "passive"))
      (node (ref "C249") (pin "1") (pinfunction "1_1") (pintype "passive"))
      (node (ref "C250") (pin "1") (pinfunction "1_1") (pintype "passive"))
      (node (ref "C251") (pin "1") (pinfunction "1_1") (pintype "passive"))
      (node (ref "C252") (pin "1") (pinfunction "1_1") (pintype "passive"))
      (node (ref "C253") (pin "1") (pinfunction "1_1") (pintype "passive"))
      (node (ref "C254") (pin "1") (pinfunction "1_1") (pintype "passive"))
      (node (ref "C255") (pin "1") (pinfunction "1_1") (pintype "passive"))
      (node (ref "C256") (pin "1") (pinfunction "1_1") (pintype "passive"))
      (node (ref "C257") (pin "1") (pinfunction "1_1") (pintype "passive"))
      (node (ref "C258") (pin "1") (pinfunction "1_1") (pintype "passive"))
      (node (ref "C259") (pin "1") (pinfunction "1_1") (pintype "passive"))
      (node (ref "C260") (pin "1") (pinfunction "1_1") (pintype "passive"))
      (node (ref "C261") (pin "1") (pinfunction "1_1") (pintype "passive"))
      (node (ref "C262") (pin "2") (pinfunction "2_2") (pintype "passive"))
      (node (ref "C263") (pin "2") (pinfunction "2_2") (pintype "passive"))
      (node (ref "C266") (pin "1") (pinfunction "1_1") (pintype "passive"))
      (node (ref "C267") (pin "2") (pinfunction "2_2") (pintype "passive"))
      (node (ref "C268") (pin "2") (pinfunction "2_2") (pintype "passive"))
      (node (ref "C269") (pin "2") (pinfunction "2_2") (pintype "passive"))
      (node (ref "C270") (pin "2") (pinfunction "2_2") (pintype "passive"))
      (node (ref "C271") (pin "1") (pinfunction "1_1") (pintype "passive"))
      (node (ref "C272") (pin "1") (pinfunction "1_1") (pintype "passive"))
      (node (ref "C273") (pin "2") (pinfunction "2_2") (pintype "passive"))
      (node (ref "C276") (pin "2") (pinfunction "2_2") (pintype "passive"))
      (node (ref "C277") (pin "1") (pinfunction "1_1") (pintype "passive"))
      (node (ref "C279") (pin "1") (pinfunction "1_1") (pintype "passive"))
      (node (ref "C280") (pin "2") (pinfunction "2_2") (pintype "passive"))
      (node (ref "C281") (pin "1") (pinfunction "1_1") (pintype "passive"))
      (node (ref "C282") (pin "2") (pinfunction "2_2") (pintype "passive"))
      (node (ref "C283") (pin "1") (pinfunction "1_1") (pintype "passive"))
      (node (ref "C284") (pin "2") (pinfunction "2_2") (pintype "passive"))
      (node (ref "IC34") (pin "1") (pinfunction "GND_1") (pintype "passive"))
      (node (ref "IC34") (pin "11") (pinfunction "GND_11") (pintype "passive"))
      (node (ref "IC34") (pin "12") (pinfunction "GND_12") (pintype "passive"))
      (node (ref "IC34") (pin "16") (pinfunction "GND_16") (pintype "passive"))
      (node (ref "IC34") (pin "19") (pinfunction "GND_19") (pintype "passive"))
      (node (ref "IC34") (pin "22") (pinfunction "SEL_22") (pintype "passive"))
      (node (ref "IC34") (pin "25") (pinfunction "GND_25") (pintype "passive"))
      (node (ref "IC34") (pin "7") (pinfunction "GND_7") (pintype "passive"))
      (node (ref "IC35") (pin "8") (pinfunction "GND_8") (pintype "passive"))
      (node (ref "IC36") (pin "1") (pinfunction "CPGND_1") (pintype "passive"))
      (node (ref "IC36") (pin "10") (pinfunction "DGND_10") (pintype "passive"))
      (node (ref "IC36") (pin "2") (pinfunction "AGND_2") (pintype "passive"))
      (node (ref "IC36") (pin "21") (pinfunction "AGND_21") (pintype "passive"))
      (node (ref "IC36") (pin "3") (pinfunction "AGND_3") (pintype "passive"))
      (node (ref "IC36") (pin "9") (pinfunction "DGND_9") (pintype "passive"))
      (node (ref "IC37") (pin "5") (pinfunction "GND_5") (pintype "power_in"))
      (node (ref "J24") (pin "2") (pinfunction "Y_2") (pintype "passive"))
      (node (ref "J25") (pin "2") (pinfunction "Y_2") (pintype "passive"))
      (node (ref "MECH4") (pin "1") (pinfunction "GND_1") (pintype "passive"))
      (node (ref "R165") (pin "1") (pinfunction "1_1") (pintype "passive"))
      (node (ref "R177") (pin "1") (pinfunction "1_1") (pintype "passive"))
      (node (ref "R183") (pin "1") (pinfunction "1_1") (pintype "passive"))
      (node (ref "R187") (pin "2") (pinfunction "2_2") (pintype "passive"))
      (node (ref "R188") (pin "2") (pinfunction "2_2") (pintype "passive"))
      (node (ref "R189") (pin "2") (pinfunction "2_2") (pintype "passive"))
      (node (ref "R190") (pin "1") (pinfunction "1_1") (pintype "passive"))
      (node (ref "R195") (pin "2") (pinfunction "2_2") (pintype "passive"))
      (node (ref "XO1") (pin "2") (pinfunction "GND_2") (pintype "passive"))
      (node (ref "XO2") (pin "2") (pinfunction "GND_2") (pintype "passive"))
      (node (ref "XO3") (pin "2") (pinfunction "GND_2") (pintype "passive"))
      (node (ref "XO4") (pin "4") (pinfunction "GND_4") (pintype "passive"))
    )
    (net (code "21") (name "Net-(C235-Pad2)") (class "Default")
      (node (ref "C235") (pin "2") (pinfunction "2_2") (pintype "passive"))
      (node (ref "C236") (pin "1") (pinfunction "1_1") (pintype "passive"))
      (node (ref "R165") (pin "2") (pinfunction "2_2") (pintype "passive"))
    )
    (net (code "22") (name "Net-(C236-Pad2)") (class "Default")
      (node (ref "C236") (pin "2") (pinfunction "2_2") (pintype "passive"))
      (node (ref "R162") (pin "1") (pinfunction "1_1") (pintype "passive"))
      (node (ref "R166") (pin "1") (pinfunction "1_1") (pintype "passive"))
      (node (ref "R168") (pin "1") (pinfunction "1_1") (pintype "passive"))
      (node (ref "R169") (pin "1") (pinfunction "1_1") (pintype "passive"))
      (node (ref "R171") (pin "1") (pinfunction "1_1") (pintype "passive"))
      (node (ref "R174") (pin "2") (pinfunction "2_2") (pintype "passive"))
    )
    (net (code "23") (name "Net-(C261-Pad2)") (class "Default")
      (node (ref "C261") (pin "2") (pinfunction "2_2") (pintype "passive"))
      (node (ref "C262") (pin "1") (pinfunction "1_1") (pintype "passive"))
      (node (ref "C263") (pin "1") (pinfunction "1_1") (pintype "passive"))
      (node (ref "FR46") (pin "2") (pinfunction "2_2") (pintype "passive"))
      (node (ref "IC36") (pin "6") (pinfunction "AVdd_6") (pintype "passive"))
      (node (ref "IC36") (pin "7") (pinfunction "AVdd_7") (pintype "passive"))
    )
    (net (code "24") (name "Net-(C264-Pad2)") (class "Default")
      (node (ref "C264") (pin "2") (pinfunction "2_2") (pintype "passive"))
      (node (ref "C265") (pin "1") (pinfunction "1_1") (pintype "passive"))
      (node (ref "R177") (pin "2") (pinfunction "2_2") (pintype "passive"))
    )
    (net (code "25") (name "Net-(C272-Pad2)") (class "Default")
      (node (ref "C272") (pin "2") (pinfunction "2_2") (pintype "passive"))
      (node (ref "R179") (pin "1") (pinfunction "1_1") (pintype "passive"))
      (node (ref "R180") (pin "2") (pinfunction "2_2") (pintype "passive"))
      (node (ref "R194") (pin "1") (pinfunction "1_1") (pintype "passive"))
      (node (ref "R195") (pin "1") (pinfunction "1_1") (pintype "passive"))
    )
    (net (code "26") (name "Net-(C274-Pad1)") (class "Default")
      (node (ref "C274") (pin "1") (pinfunction "1_1") (pintype "passive"))
      (node (ref "C275") (pin "2") (pinfunction "2_2") (pintype "passive"))
      (node (ref "R183") (pin "2") (pinfunction "2_2") (pintype "passive"))
    )
    (net (code "27") (name "Net-(C277-Pad2)") (class "Default")
      (node (ref "C277") (pin "2") (pinfunction "2_2") (pintype "passive"))
      (node (ref "R182") (pin "2") (pinfunction "2_2") (pintype "passive"))
      (node (ref "R184") (pin "1") (pinfunction "1_1") (pintype "passive"))
    )
    (net (code "28") (name "Net-(C278-Pad1)") (class "Default")
      (node (ref "C278") (pin "1") (pinfunction "1_1") (pintype "passive"))
      (node (ref "R190") (pin "2") (pinfunction "2_2") (pintype "passive"))
    )
    (net (code "29") (name "Net-(FR42-Pad2)") (class "Default")
      (node (ref "FR42") (pin "2") (pinfunction "2_2") (pintype "passive"))
      (node (ref "R163") (pin "1") (pinfunction "1_1") (pintype "passive"))
      (node (ref "R172") (pin "2") (pinfunction "2_2") (pintype "passive"))
      (node (ref "R173") (pin "1") (pinfunction "1_1") (pintype "passive"))
    )
    (net (code "30") (name "Net-(IC34-CLKin)") (class "Default")
      (node (ref "C235") (pin "1") (pinfunction "1_1") (pintype "passive"))
      (node (ref "IC34") (pin "21") (pinfunction "CLKin_21") (pintype "passive"))
    )
    (net (code "31") (name "Net-(IC34-CLKin*)") (class "Default")
      (node (ref "C240") (pin "2") (pinfunction "2_2") (pintype "passive"))
      (node (ref "IC34") (pin "20") (pinfunction "CLKin*_20") (pintype "passive"))
    )
    (net (code "32") (name "Net-(IC34-CLKout0)") (class "Default")
      (node (ref "IC34") (pin "3") (pinfunction "CLKout0_3") (pintype "passive"))
      (node (ref "R164") (pin "2") (pinfunction "2_2") (pintype "passive"))
    )
    (net (code "33") (name "Net-(IC34-CLKout1)") (class "Default")
      (node (ref "IC34") (pin "5") (pinfunction "CLKout1_5") (pintype "passive"))
      (node (ref "R167") (pin "2") (pinfunction "2_2") (pintype "passive"))
    )
    (net (code "34") (name "Net-(IC34-OE)") (class "Default")
      (node (ref "IC34") (pin "24") (pinfunction "OE_24") (pintype "passive"))
      (node (ref "R161") (pin "1") (pinfunction "1_1") (pintype "passive"))
    )
    (net (code "35") (name "Net-(IC35-Vdd)") (class "Default")
      (node (ref "C266") (pin "2") (pinfunction "2_2") (pintype "passive"))
      (node (ref "C267") (pin "1") (pinfunction "1_1") (pintype "passive"))
      (node (ref "C268") (pin "1") (pinfunction "1_1") (pintype "passive"))
      (node (ref "C284") (pin "1") (pinfunction "1_1") (pintype "passive"))
      (node (ref "FR47") (pin "1") (pinfunction "1_1") (pintype "passive"))
      (node (ref "IC35") (pin "1") (pinfunction "Vdd_1") (pintype "power_in"))
      (node (ref "IC37") (pin "4") (pinfunction "VDD_4") (pintype "power_in"))
      (node (ref "R185") (pin "2") (pinfunction "2_2") (pintype "passive"))
    )
    (net (code "36") (name "Net-(IC35-Vfb)") (class "Default")
      (node (ref "C276") (pin "1") (pinfunction "1_1") (pintype "passive"))
      (node (ref "IC35") (pin "3") (pinfunction "Vfb_3") (pintype "input"))
      (node (ref "IC35") (pin "4") (pinfunction "Vout_4") (pintype "output"))
      (node (ref "R179") (pin "2") (pinfunction "2_2") (pintype "passive"))
    )
    (net (code "37") (name "Net-(IC36-CE)") (class "Default")
      (node (ref "IC36") (pin "11") (pinfunction "CE_11") (pintype "passive"))
      (node (ref "R181") (pin "1") (pinfunction "1_1") (pintype "passive"))
    )
    (net (code "38") (name "Net-(IC36-CLK)") (class "Default")
      (node (ref "C283") (pin "2") (pinfunction "2_2") (pintype "passive"))
      (node (ref "IC36") (pin "12") (pinfunction "CLK_12") (pintype "passive"))
      (node (ref "R191") (pin "2") (pinfunction "2_2") (pintype "passive"))
    )
    (net (code "39") (name "Net-(IC36-CP)") (class "Default")
      (node (ref "C278") (pin "2") (pinfunction "2_2") (pintype "passive"))
      (node (ref "C279") (pin "2") (pinfunction "2_2") (pintype "passive"))
      (node (ref "IC36") (pin "20") (pinfunction "CP_20") (pintype "passive"))
      (node (ref "R182") (pin "1") (pinfunction "1_1") (pintype "passive"))
    )
    (net (code "40") (name "Net-(IC36-DATA)") (class "Default")
      (node (ref "IC36") (pin "13") (pinfunction "DATA_13") (pintype "passive"))
      (node (ref "R192") (pin "2") (pinfunction "2_2") (pintype "passive"))
    )
    (net (code "41") (name "Net-(IC36-LE)") (class "Default")
      (node (ref "IC36") (pin "14") (pinfunction "LE_14") (pintype "passive"))
      (node (ref "R193") (pin "2") (pinfunction "2_2") (pintype "passive"))
    )
    (net (code "42") (name "Net-(IC36-REFin)") (class "Default")
      (node (ref "C274") (pin "2") (pinfunction "2_2") (pintype "passive"))
      (node (ref "IC36") (pin "8") (pinfunction "REFin_8") (pintype "passive"))
    )
    (net (code "43") (name "Net-(IC36-RFinA)") (class "Default")
      (node (ref "C264") (pin "1") (pinfunction "1_1") (pintype "passive"))
      (node (ref "IC36") (pin "5") (pinfunction "RFinA_5") (pintype "passive"))
    )
    (net (code "44") (name "Net-(IC36-RFinB)") (class "Default")
      (node (ref "C280") (pin "1") (pinfunction "1_1") (pintype "passive"))
      (node (ref "IC36") (pin "4") (pinfunction "RFinB_4") (pintype "passive"))
    )
    (net (code "45") (name "Net-(IC36-Rset)") (class "Default")
      (node (ref "IC36") (pin "19") (pinfunction "Rset_19") (pintype "passive"))
      (node (ref "R189") (pin "1") (pinfunction "1_1") (pintype "passive"))
    )
    (net (code "46") (name "Net-(IC36-Vp)") (class "Default")
      (node (ref "C271") (pin "2") (pinfunction "2_2") (pintype "passive"))
      (node (ref "C273") (pin "1") (pinfunction "1_1") (pintype "passive"))
      (node (ref "IC36") (pin "18") (pinfunction "Vp_18") (pintype "passive"))
      (node (ref "R178") (pin "1") (pinfunction "1_1") (pintype "passive"))
    )
    (net (code "47") (name "Net-(IC37-VOUT)") (class "Default")
      (node (ref "IC37") (pin "6") (pinfunction "VOUT_6") (pintype "tri_state"))
      (node (ref "R194") (pin "2") (pinfunction "2_2") (pintype "passive"))
    )
    (net (code "48") (name "Net-(J24-X)") (class "Default")
      (node (ref "J24") (pin "1") (pinfunction "X_1") (pintype "passive"))
      (node (ref "R176") (pin "1") (pinfunction "1_1") (pintype "passive"))
    )
    (net (code "49") (name "Net-(R173-Pad2)") (class "Default")
      (node (ref "R173") (pin "2") (pinfunction "2_2") (pintype "passive"))
      (node (ref "R175") (pin "1") (pinfunction "1_1") (pintype "passive"))
    )
    (net (code "50") (name "Net-(XO1-Output)") (class "Default")
      (node (ref "R162") (pin "2") (pinfunction "2_2") (pintype "passive"))
      (node (ref "XO1") (pin "3") (pinfunction "Output_3") (pintype "output"))
    )
    (net (code "51") (name "Net-(XO1-Vcc)") (class "Default")
      (node (ref "C237") (pin "2") (pinfunction "2_2") (pintype "passive"))
      (node (ref "C238") (pin "2") (pinfunction "2_2") (pintype "passive"))
      (node (ref "C239") (pin "1") (pinfunction "1_1") (pintype "passive"))
      (node (ref "R163") (pin "2") (pinfunction "2_2") (pintype "passive"))
      (node (ref "XO1") (pin "4") (pinfunction "Vcc_4") (pintype "power_in"))
    )
    (net (code "52") (name "Net-(XO2-OUT)") (class "Default")
      (node (ref "R171") (pin "2") (pinfunction "2_2") (pintype "passive"))
      (node (ref "XO2") (pin "4") (pinfunction "OUT_4") (pintype "passive"))
      (node (ref "XO3") (pin "3") (pinfunction "OUT_3") (pintype "passive"))
    )
    (net (code "53") (name "Net-(XO2-TRI-ST.)") (class "Default")
      (node (ref "R170") (pin "1") (pinfunction "1_1") (pintype "passive"))
      (node (ref "XO2") (pin "6") (pinfunction "TRI-ST._6") (pintype "passive"))
    )
    (net (code "54") (name "Net-(XO2-VDD)") (class "Default")
      (node (ref "C255") (pin "2") (pinfunction "2_2") (pintype "passive"))
      (node (ref "C256") (pin "2") (pinfunction "2_2") (pintype "passive"))
      (node (ref "R170") (pin "2") (pinfunction "2_2") (pintype "passive"))
      (node (ref "R172") (pin "1") (pinfunction "1_1") (pintype "passive"))
      (node (ref "XO2") (pin "5") (pinfunction "VDD_5") (pintype "passive"))
      (node (ref "XO3") (pin "4") (pinfunction "VDD_4") (pintype "passive"))
    )
    (net (code "55") (name "Net-(XO4-RF_OUT)") (class "Default")
      (node (ref "R174") (pin "1") (pinfunction "1_1") (pintype "passive"))
      (node (ref "XO4") (pin "6") (pinfunction "RF_OUT_6") (pintype "output"))
    )
    (net (code "56") (name "Net-(XO4-VCC)") (class "Default")
      (node (ref "C257") (pin "2") (pinfunction "2_2") (pintype "passive"))
      (node (ref "C258") (pin "2") (pinfunction "2_2") (pintype "passive"))
      (node (ref "R175") (pin "2") (pinfunction "2_2") (pintype "passive"))
      (node (ref "XO4") (pin "9") (pinfunction "VCC_9") (pintype "power_in"))
    )
    (net (code "57") (name "Net-(XO4-VC_FILTER)") (class "Default")
      (node (ref "C259") (pin "2") (pinfunction "2_2") (pintype "passive"))
      (node (ref "XO4") (pin "7") (pinfunction "VC_FILTER_7") (pintype "input"))
    )
    (net (code "58") (name "VCC1P8_2") (class "Default")
      (node (ref "FR45") (pin "1") (pinfunction "1_1") (pintype "passive"))
    )
    (net (code "59") (name "VCC2P5") (class "Default")
      (node (ref "R186") (pin "2") (pinfunction "2_2") (pintype "passive"))
    )
    (net (code "60") (name "VCC3P3_CLK") (class "Default")
      (node (ref "C260") (pin "2") (pinfunction "2_2") (pintype "passive"))
      (node (ref "C269") (pin "1") (pinfunction "1_1") (pintype "passive"))
      (node (ref "C270") (pin "1") (pinfunction "1_1") (pintype "passive"))
      (node (ref "FR42") (pin "1") (pinfunction "1_1") (pintype "passive"))
      (node (ref "FR43") (pin "1") (pinfunction "1_1") (pintype "passive"))
      (node (ref "FR44") (pin "1") (pinfunction "1_1") (pintype "passive"))
      (node (ref "FR46") (pin "1") (pinfunction "1_1") (pintype "passive"))
      (node (ref "FR47") (pin "2") (pinfunction "2_2") (pintype "passive"))
      (node (ref "IC36") (pin "16") (pinfunction "DVdd_16") (pintype "passive"))
      (node (ref "IC36") (pin "17") (pinfunction "DVdd_17") (pintype "passive"))
      (node (ref "R178") (pin "2") (pinfunction "2_2") (pintype "passive"))
      (node (ref "R181") (pin "2") (pinfunction "2_2") (pintype "passive"))
    )
    (net (code "61") (name "VCC3P3_LMK") (class "Default")
      (node (ref "C248") (pin "2") (pinfunction "2_2") (pintype "passive"))
      (node (ref "C249") (pin "2") (pinfunction "2_2") (pintype "passive"))
      (node (ref "C250") (pin "2") (pinfunction "2_2") (pintype "passive"))
      (node (ref "C251") (pin "2") (pinfunction "2_2") (pintype "passive"))
      (node (ref "FR44") (pin "2") (pinfunction "2_2") (pintype "passive"))
      (node (ref "IC34") (pin "23") (pinfunction "Vdd_23") (pintype "passive"))
      (node (ref "IC34") (pin "8") (pinfunction "Vdd_8") (pintype "passive"))
      (node (ref "R161") (pin "2") (pinfunction "2_2") (pintype "passive"))
    )
    (net (code "62") (name "VCC3P3_LMK2") (class "Default")
      (node (ref "C243") (pin "2") (pinfunction "2_2") (pintype "passive"))
      (node (ref "C244") (pin "2") (pinfunction "2_2") (pintype "passive"))
      (node (ref "C245") (pin "2") (pinfunction "2_2") (pintype "passive"))
      (node (ref "C246") (pin "2") (pinfunction "2_2") (pintype "passive"))
      (node (ref "FR43") (pin "2") (pinfunction "2_2") (pintype "passive"))
      (node (ref "IC34") (pin "14") (pinfunction "Vddo_14") (pintype "passive"))
      (node (ref "IC34") (pin "18") (pinfunction "Vddo_18") (pintype "passive"))
    )
    (net (code "63") (name "unconnected-(IC34-OSCin-Pad9)") (class "Default")
      (node (ref "IC34") (pin "9") (pinfunction "OSCin_9") (pintype "passive+no_connect"))
    )
    (net (code "64") (name "unconnected-(IC34-OSCout-Pad10)") (class "Default")
      (node (ref "IC34") (pin "10") (pinfunction "OSCout_10") (pintype "passive+no_connect"))
    )
    (net (code "65") (name "unconnected-(XO2-T.S.-Pad3)") (class "Default")
      (node (ref "XO2") (pin "3") (pinfunction "T.S._3") (pintype "passive+no_connect"))
    )
    (net (code "66") (name "unconnected-(XO4-NC-Pad2)") (class "Default")
      (node (ref "XO4") (pin "2") (pinfunction "NC_2") (pintype "passive+no_connect"))
    )
    (net (code "67") (name "unconnected-(XO4-NC-Pad3)") (class "Default")
      (node (ref "XO4") (pin "3") (pinfunction "NC_3") (pintype "passive+no_connect"))
    )
    (net (code "68") (name "unconnected-(XO4-NC-Pad5)") (class "Default")
      (node (ref "XO4") (pin "5") (pinfunction "NC_5") (pintype "passive+no_connect"))
    )
    (net (code "69") (name "unconnected-(XO4-NC-Pad8)") (class "Default")
      (node (ref "XO4") (pin "8") (pinfunction "NC_8") (pintype "passive+no_connect"))
    )
    (net (code "70") (name "unconnected-(XO4-NC-Pad10)") (class "Default")
      (node (ref "XO4") (pin "10") (pinfunction "NC_10") (pintype "passive+no_connect"))
    )
  )
)
